# Finalpart2.net
KiCad netlist of a schematic drawn in EAGLE
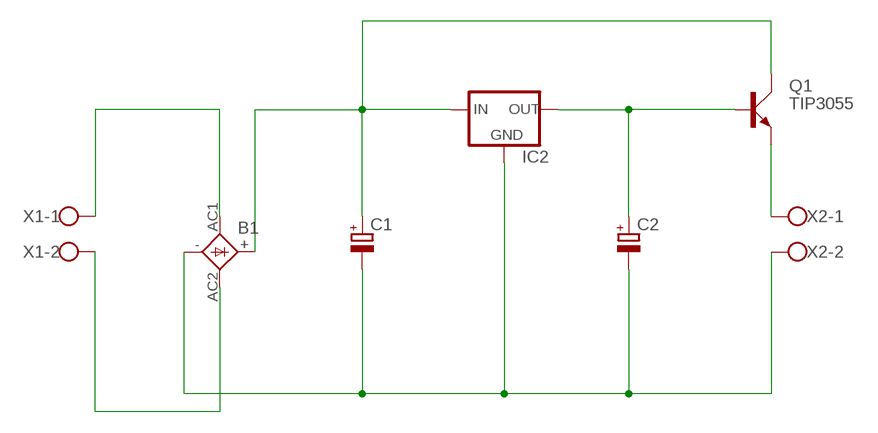
[diagram p0: schematic, sheet 1]

(export (version "E")
  (design (tool "Eeschema 10.0.6"))
  (components
    (comp (ref "B1")
      (value "FB32")
      (footprint "eagle-import:FB32")
      (libsource (lib "eagle-import") (part "FB32"))
    )
    (comp (ref "C1")
      (value "CPOL-EUE7.5-16")
      (footprint "eagle-import:E7,5-16")
      (libsource (lib "eagle-import") (part "CPOL-EUE7.5-16"))
    )
    (comp (ref "C2")
      (value "CPOL-EUE3.5-8")
      (footprint "eagle-import:E3,5-8")
      (libsource (lib "eagle-import") (part "CPOL-EUE3.5-8"))
    )
    (comp (ref "IC2")
      (value "78XXL")
      (footprint "eagle-import:78XXL")
      (libsource (lib "eagle-import") (part "78XXL"))
    )
    (comp (ref "Q1")
      (value "TIP3055")
      (footprint "eagle-import:TOP3AV")
      (libsource (lib "eagle-import") (part "TIP3055"))
    )
    (comp (ref "X1")
      (value "W237-102")
      (footprint "eagle-import:W237-102")
      (fields (field (name "MPN") "237-102"))
      (libsource (lib "eagle-import") (part "W237-102"))
    )
    (comp (ref "X2")
      (value "W237-102")
      (footprint "eagle-import:W237-102")
      (fields (field (name "MPN") "237-102"))
      (libsource (lib "eagle-import") (part "W237-102"))
    )
  )
  (nets
    (net (code "1") (name "Net-(B1-Pad+)") (class "Default")
      (node (ref "B1") (pin "+") (pinfunction "+_+") (pintype "passive"))
      (node (ref "C1") (pin "+") (pinfunction "+_+") (pintype "passive"))
      (node (ref "IC2") (pin "IN") (pinfunction "IN_IN") (pintype "input"))
      (node (ref "Q1") (pin "C") (pinfunction "C_C") (pintype "passive"))
    )
    (net (code "2") (name "Net-(C2-Pad+)") (class "Default")
      (node (ref "C2") (pin "+") (pinfunction "+_+") (pintype "passive"))
      (node (ref "IC2") (pin "OUT") (pinfunction "OUT_OUT") (pintype "passive"))
      (node (ref "Q1") (pin "B") (pinfunction "B_B") (pintype "passive"))
    )
    (net (code "3") (name "Net-(X1A-KL)") (class "Default")
      (node (ref "B1") (pin "AC1") (pinfunction "AC1_AC1") (pintype "passive"))
      (node (ref "X1") (pin "1") (pinfunction "KL_1") (pintype "passive"))
    )
    (net (code "4") (name "Net-(X1B-KL)") (class "Default")
      (node (ref "B1") (pin "AC2") (pinfunction "AC2_AC2") (pintype "passive"))
      (node (ref "X1") (pin "2") (pinfunction "KL_2") (pintype "passive"))
    )
    (net (code "5") (name "Net-(X2A-KL)") (class "Default")
      (node (ref "Q1") (pin "E") (pinfunction "E_E") (pintype "passive"))
      (node (ref "X2") (pin "1") (pinfunction "KL_1") (pintype "passive"))
    )
    (net (code "6") (name "Net-(X2B-KL)") (class "Default")
      (node (ref "B1") (pin "-") (pinfunction "-_-") (pintype "passive"))
      (node (ref "C1") (pin "-") (pinfunction "-_-") (pintype "passive"))
      (node (ref "C2") (pin "-") (pinfunction "-_-") (pintype "passive"))
      (node (ref "IC2") (pin "GND") (pinfunction "GND_GND") (pintype "input"))
      (node (ref "X2") (pin "2") (pinfunction "KL_2") (pintype "passive"))
    )
  )
)
